# Driver.net
KiCad netlist of a schematic drawn in Altium Designer
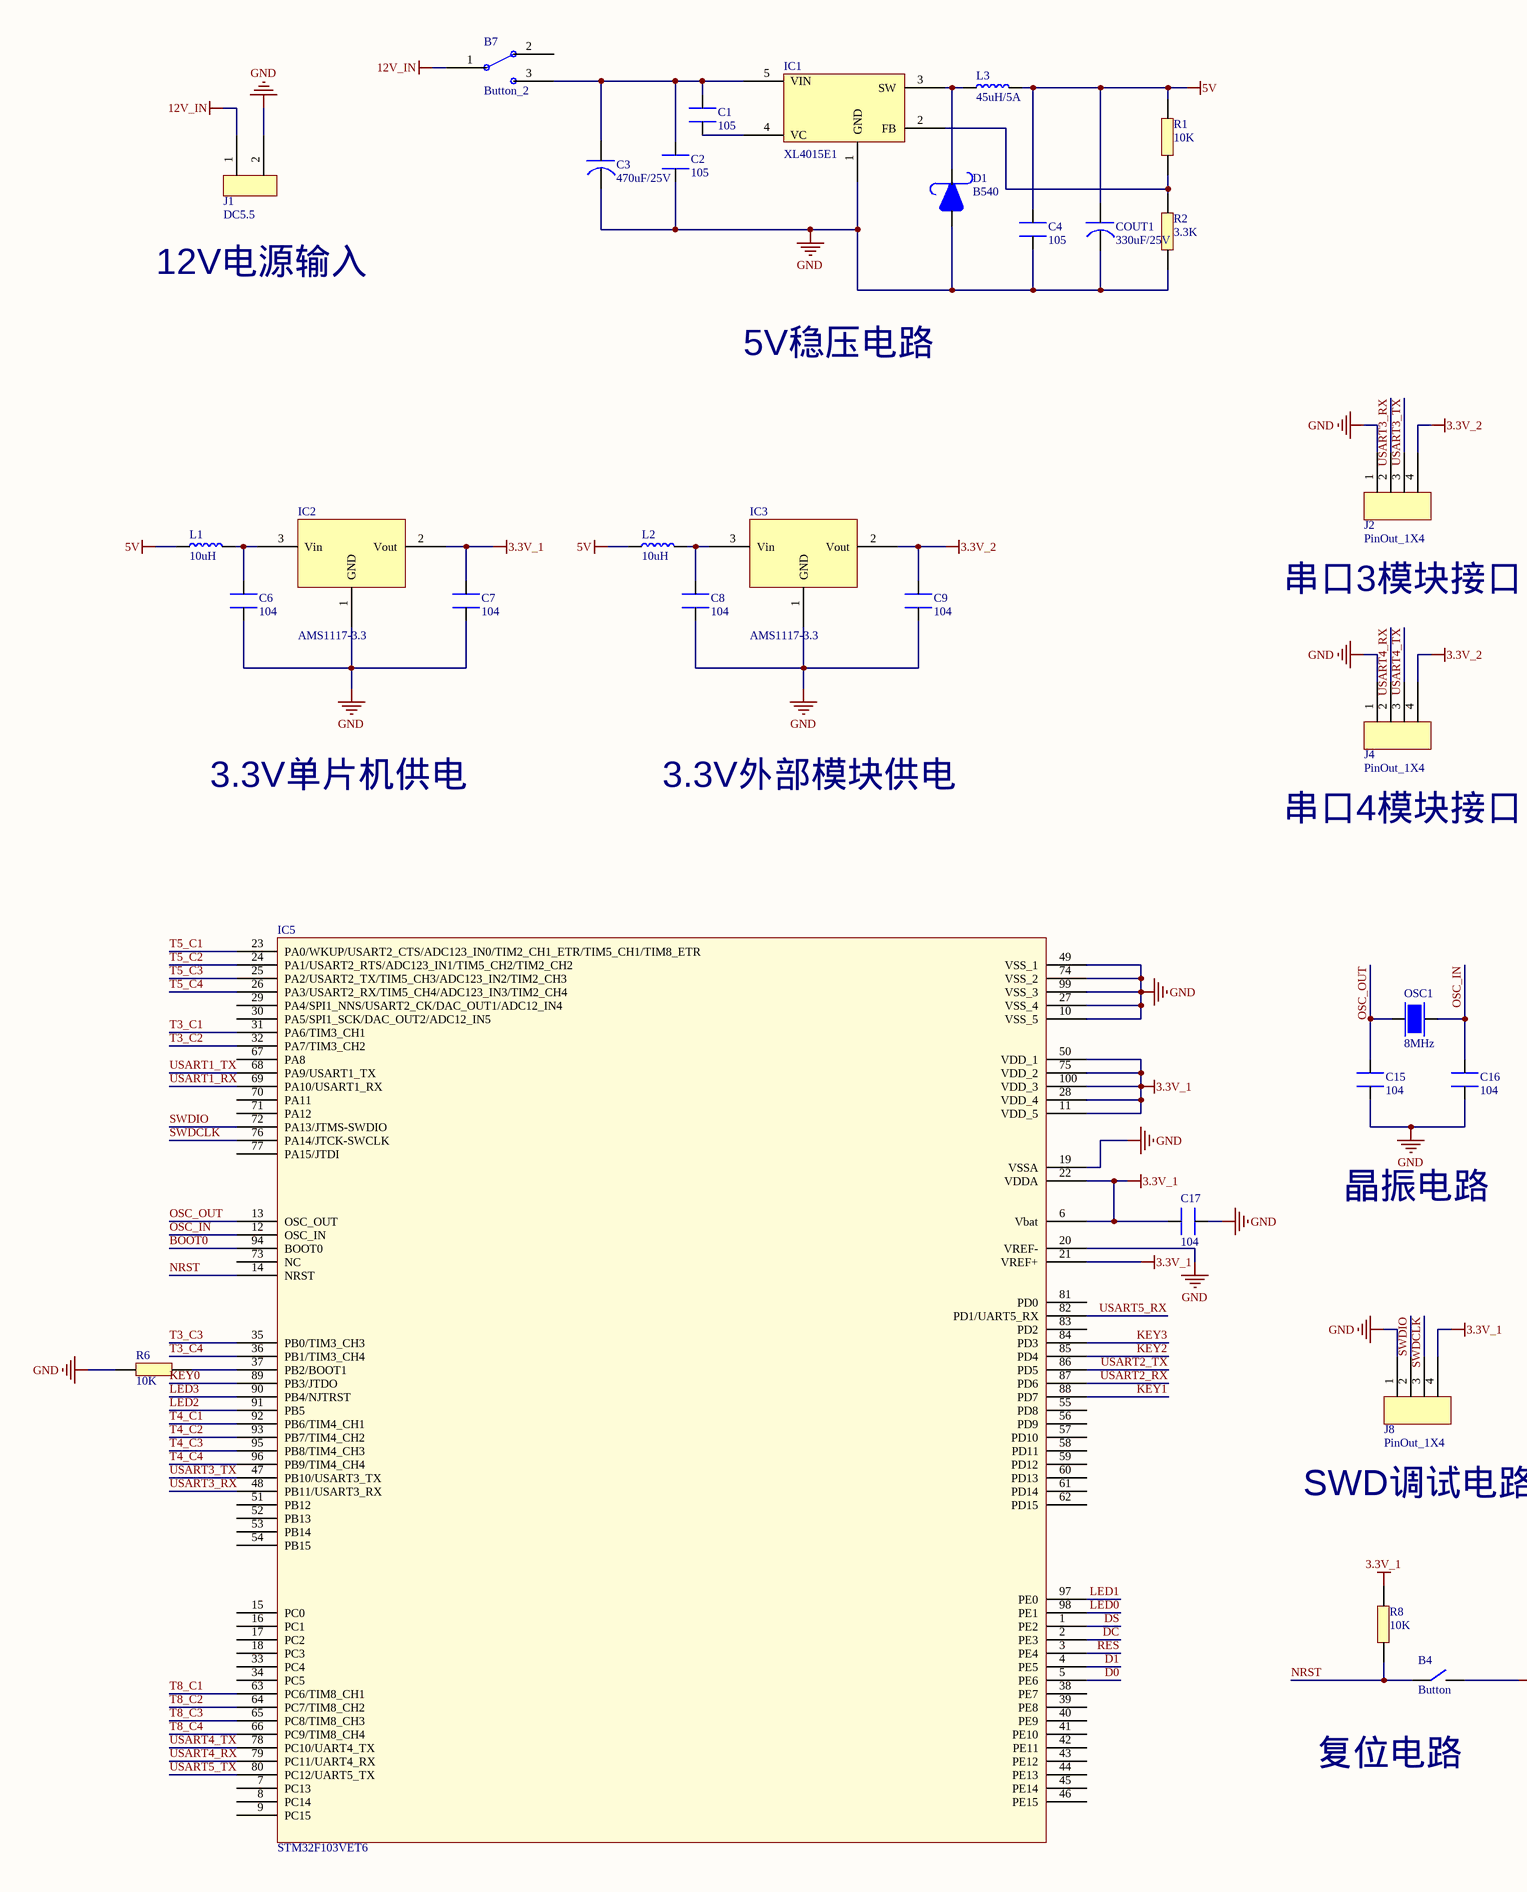
[diagram p0: Driver.SchDoc, left]
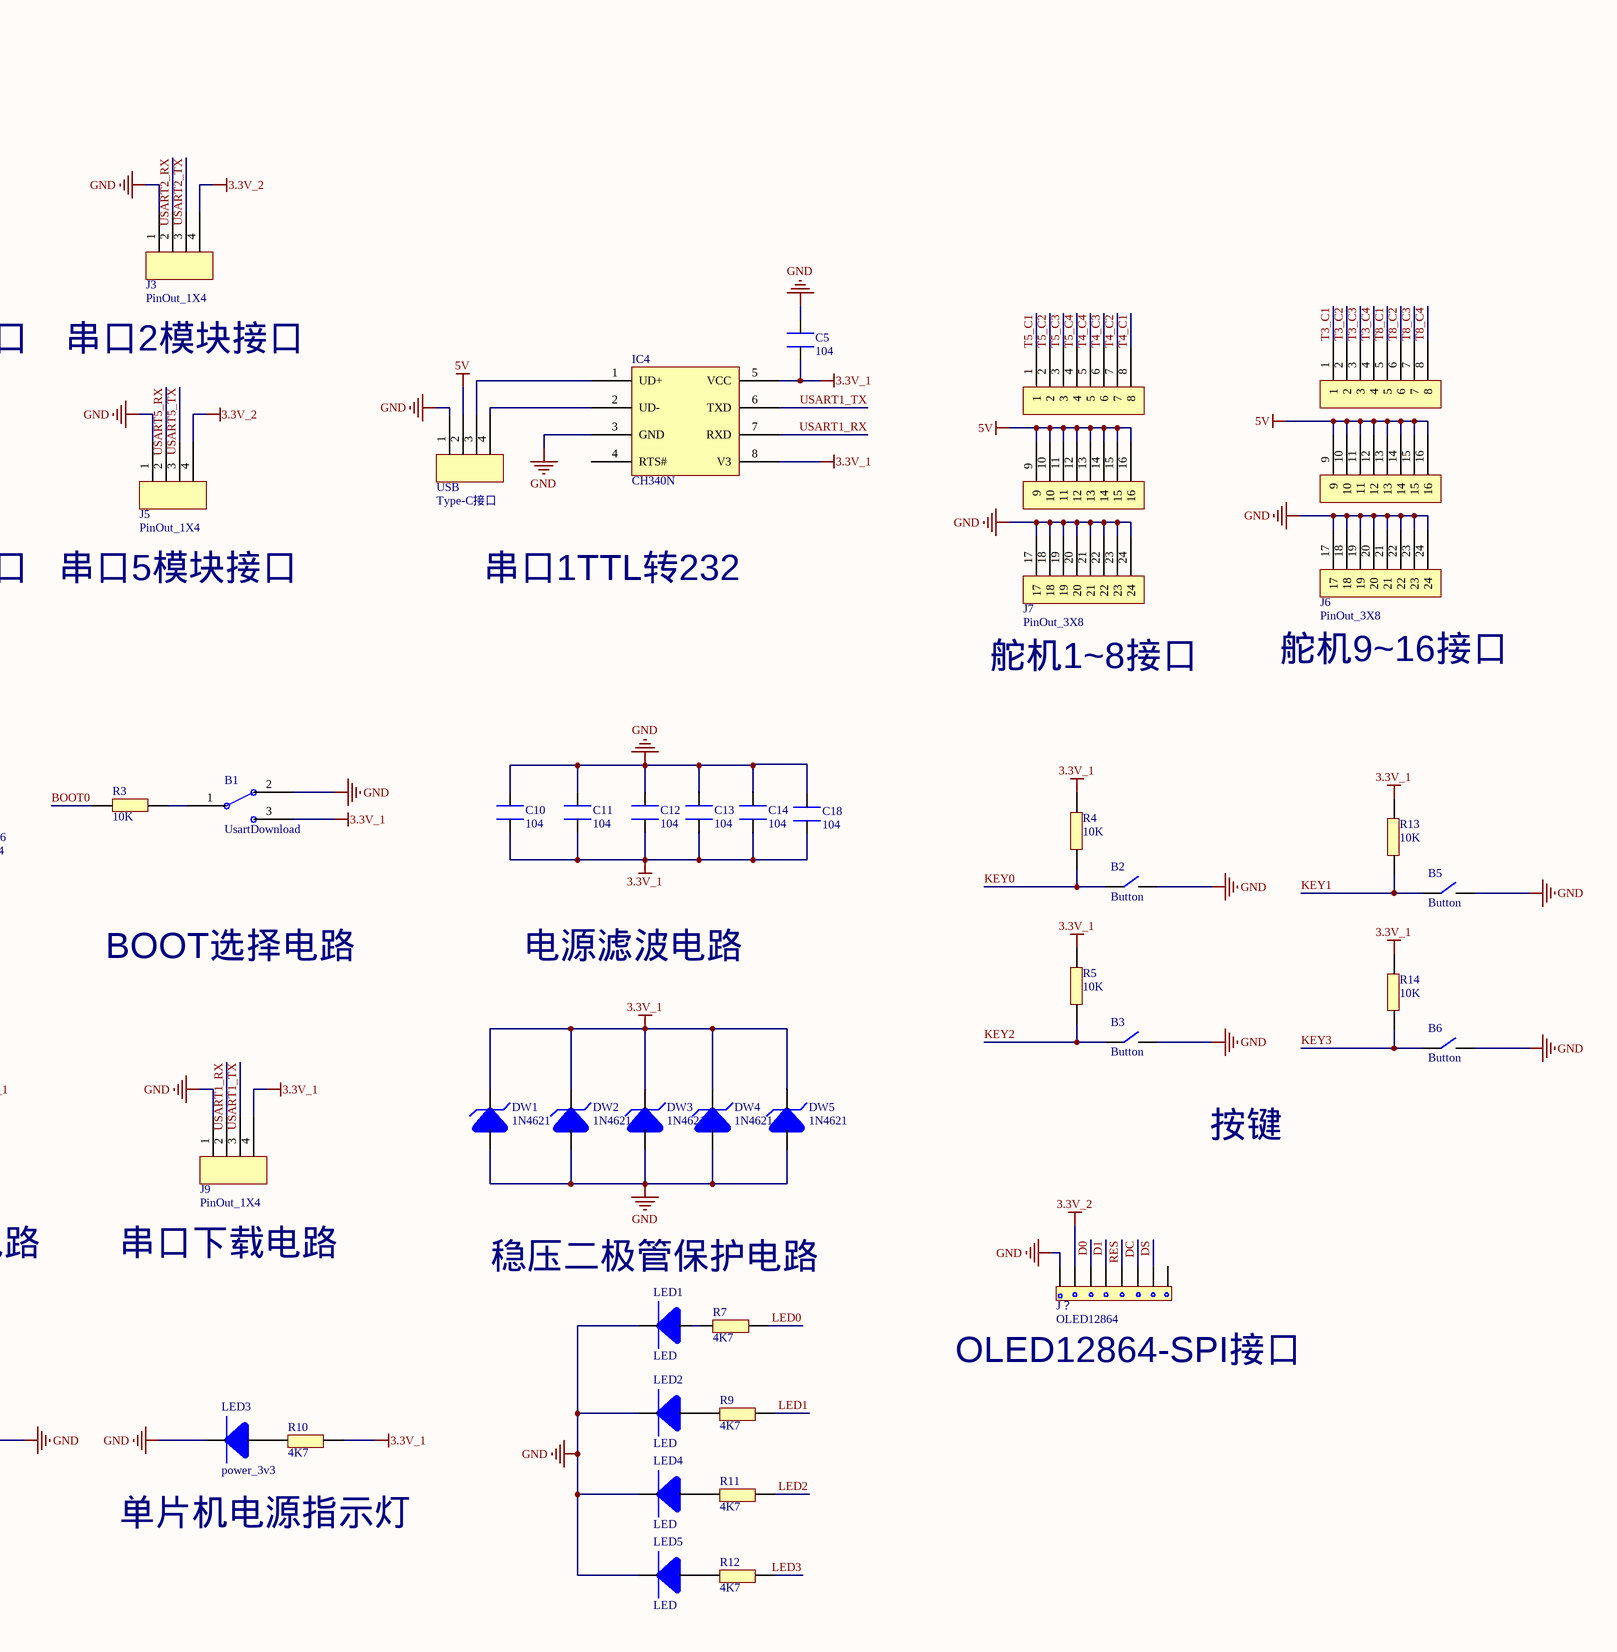
[diagram p1: Driver.SchDoc, right]

(export (version "E")
  (design (tool "Eeschema 10.0.6"))
  (components
    (comp (ref "B1")
      (value "UsartDownload")
      (footprint "BUTTON_7X7")
      (libsource (lib "altium-import") (part "root_0_Button_2_"))
    )
    (comp (ref "B2") (value "Button") (footprint "BUTTON") (libsource (lib "Driver") (part "Button")))
    (comp (ref "B3") (value "Button") (footprint "BUTTON") (libsource (lib "Driver") (part "Button")))
    (comp (ref "B4") (value "Button") (footprint "BUTTON") (libsource (lib "Driver") (part "Button")))
    (comp (ref "B5") (value "Button") (footprint "BUTTON") (libsource (lib "Driver") (part "Button")))
    (comp (ref "B6") (value "Button") (footprint "BUTTON") (libsource (lib "Driver") (part "Button")))
    (comp (ref "B7") (value "Button_2") (footprint "BUTTON_7X7") (libsource (lib "Driver") (part "Button_2")))
    (comp (ref "C1") (value "105") (footprint "0805") (libsource (lib "Driver") (part "CAP")))
    (comp (ref "C2") (value "105") (footprint "0805") (libsource (lib "Driver") (part "CAP")))
    (comp (ref "C3") (value "470uF/25V") (footprint "CM D(6.3X7.7)") (libsource (lib "Driver") (part "TAN")))
    (comp (ref "C4") (value "105") (footprint "0805") (libsource (lib "Driver") (part "CAP")))
    (comp (ref "C5") (value "104") (footprint "0805") (libsource (lib "Driver") (part "CAP")))
    (comp (ref "C6") (value "104") (footprint "0805") (libsource (lib "altium-import") (part "root_3_CAP_")))
    (comp (ref "C7") (value "104") (footprint "0805") (libsource (lib "altium-import") (part "root_3_CAP_")))
    (comp (ref "C8") (value "104") (footprint "0805") (libsource (lib "altium-import") (part "root_3_CAP_")))
    (comp (ref "C9") (value "104") (footprint "0805") (libsource (lib "altium-import") (part "root_3_CAP_")))
    (comp (ref "C10") (value "104") (footprint "0805") (libsource (lib "Driver") (part "CAP")))
    (comp (ref "C11") (value "104") (footprint "0805") (libsource (lib "Driver") (part "CAP")))
    (comp (ref "C12") (value "104") (footprint "0805") (libsource (lib "Driver") (part "CAP")))
    (comp (ref "C13") (value "104") (footprint "0805") (libsource (lib "Driver") (part "CAP")))
    (comp (ref "C14") (value "104") (footprint "0805") (libsource (lib "Driver") (part "CAP")))
    (comp (ref "C15") (value "104") (footprint "0805") (libsource (lib "Driver") (part "CAP")))
    (comp (ref "C16") (value "104") (footprint "0805") (libsource (lib "Driver") (part "CAP")))
    (comp (ref "C17") (value "104") (footprint "0805") (libsource (lib "Driver") (part "CAP")))
    (comp (ref "C18") (value "104") (footprint "0805") (libsource (lib "Driver") (part "CAP")))
    (comp (ref "COUT1")
      (value "330uF/25V")
      (footprint "CM D(6.3X7.7)")
      (libsource (lib "Driver") (part "TAN"))
    )
    (comp (ref "D1") (value "B540") (footprint "SMA/DO-214AC") (libsource (lib "Driver") (part "SBD")))
    (comp (ref "DW1") (value "1N4621") (footprint "1206") (libsource (lib "Driver") (part "DW")))
    (comp (ref "DW2") (value "1N4621") (footprint "1206") (libsource (lib "Driver") (part "DW")))
    (comp (ref "DW3") (value "1N4621") (footprint "1206") (libsource (lib "Driver") (part "DW")))
    (comp (ref "DW4") (value "1N4621") (footprint "1206") (libsource (lib "Driver") (part "DW")))
    (comp (ref "DW5") (value "1N4621") (footprint "1206") (libsource (lib "Driver") (part "DW")))
    (comp (ref "IC1") (value "XL4015E1") (footprint "TO236-5") (libsource (lib "Driver") (part "XL4015E1")))
    (comp (ref "IC2")
      (value "AMS1117-3.3")
      (footprint "AMS1117")
      (libsource (lib "Driver") (part "AMS1117-3.3"))
    )
    (comp (ref "IC3")
      (value "AMS1117-3.3")
      (footprint "AMS1117")
      (libsource (lib "Driver") (part "AMS1117-3.3"))
    )
    (comp (ref "IC4") (value "CH340N") (footprint "SOP-8") (libsource (lib "Driver") (part "CH340N")))
    (comp (ref "IC5")
      (value "STM32F103VET6")
      (footprint "LQFP100-14X14")
      (libsource (lib "altium-import") (part "root_0_STM32F103VET6_"))
    )
    (comp (ref "J1") (value "DC5.5") (footprint "DC_5.5") (libsource (lib "Driver") (part "PinOut_1X2")))
    (comp (ref "J2") (value "PinOut_1X4") (footprint "MX1.25") (libsource (lib "Driver") (part "PinOut_1X4")))
    (comp (ref "J3") (value "PinOut_1X4") (footprint "MX1.25") (libsource (lib "Driver") (part "PinOut_1X4")))
    (comp (ref "J4") (value "PinOut_1X4") (footprint "MX1.25") (libsource (lib "Driver") (part "PinOut_1X4")))
    (comp (ref "J5") (value "PinOut_1X4") (footprint "MX1.25") (libsource (lib "Driver") (part "PinOut_1X4")))
    (comp (ref "J6")
      (value "PinOut_3X8")
      (footprint "HEAD_3X8")
      (libsource (lib "Driver") (part "PinOut_3X8"))
    )
    (comp (ref "J7")
      (value "PinOut_3X8")
      (footprint "HEAD_3X8")
      (libsource (lib "Driver") (part "PinOut_3X8"))
    )
    (comp (ref "J8") (value "PinOut_1X4") (footprint "MX1.25") (libsource (lib "Driver") (part "PinOut_1X4")))
    (comp (ref "J9") (value "PinOut_1X4") (footprint "MX1.25") (libsource (lib "Driver") (part "PinOut_1X4")))
    (comp (ref "J？")
      (value "OLED12864")
      (footprint "HEAD_1X8")
      (libsource (lib "Driver") (part "PinOut_1X8"))
    )
    (comp (ref "L1") (value "10uH") (footprint "0630") (libsource (lib "Driver") (part "IND")))
    (comp (ref "L2") (value "10uH") (footprint "0630") (libsource (lib "Driver") (part "IND")))
    (comp (ref "L3") (value "45uH/5A") (footprint "0630") (libsource (lib "Driver") (part "IND")))
    (comp (ref "LED1") (value "LED") (footprint "1206") (libsource (lib "Driver") (part "LED")))
    (comp (ref "LED2") (value "LED") (footprint "1206") (libsource (lib "Driver") (part "LED")))
    (comp (ref "LED3") (value "power_3v3") (footprint "1206") (libsource (lib "Driver") (part "LED")))
    (comp (ref "LED4") (value "LED") (footprint "1206") (libsource (lib "Driver") (part "LED")))
    (comp (ref "LED5") (value "LED") (footprint "1206") (libsource (lib "Driver") (part "LED")))
    (comp (ref "OSC1") (value "8MHz") (footprint "OSC") (libsource (lib "Driver") (part "OSC")))
    (comp (ref "R1") (value "10K") (footprint "0805") (libsource (lib "") (part "RES_1")))
    (comp (ref "R2") (value "3.3K") (footprint "0805") (libsource (lib "") (part "RES_1")))
    (comp (ref "R3") (value "10K") (footprint "0805") (libsource (lib "Driver") (part "RES")))
    (comp (ref "R4") (value "10K") (footprint "0805") (libsource (lib "") (part "RES_1")))
    (comp (ref "R5") (value "10K") (footprint "0805") (libsource (lib "") (part "RES_1")))
    (comp (ref "R6") (value "10K") (footprint "0805") (libsource (lib "Driver") (part "RES")))
    (comp (ref "R7") (value "4K7") (footprint "0805") (libsource (lib "") (part "RES_2")))
    (comp (ref "R8") (value "10K") (footprint "0805") (libsource (lib "") (part "RES_1")))
    (comp (ref "R9") (value "4K7") (footprint "0805") (libsource (lib "") (part "RES_2")))
    (comp (ref "R10") (value "4K7") (footprint "0805") (libsource (lib "") (part "RES_2")))
    (comp (ref "R11") (value "4K7") (footprint "0805") (libsource (lib "") (part "RES_2")))
    (comp (ref "R12") (value "4K7") (footprint "0805") (libsource (lib "") (part "RES_2")))
    (comp (ref "R13") (value "10K") (footprint "0805") (libsource (lib "") (part "RES_1")))
    (comp (ref "R14") (value "10K") (footprint "0805") (libsource (lib "") (part "RES_1")))
    (comp (ref "USB") (value "Type-C接口") (footprint "Type-C") (libsource (lib "Driver") (part "PinOut_1X4")))
  )
  (nets
    (net (code "1") (name "/BOOT0") (class "Default")
      (node (ref "IC5") (pin "94") (pinfunction "BOOT0_94") (pintype "passive"))
      (node (ref "R3") (pin "1") (pinfunction "1_1") (pintype "passive"))
    )
    (net (code "2") (name "/D0") (class "Default")
      (node (ref "IC5") (pin "5") (pinfunction "PE6_5") (pintype "passive"))
      (node (ref "J？") (pin "3") (pinfunction "3_3") (pintype "passive"))
    )
    (net (code "3") (name "/D1") (class "Default")
      (node (ref "IC5") (pin "4") (pinfunction "PE5_4") (pintype "passive"))
      (node (ref "J？") (pin "4") (pinfunction "4_4") (pintype "passive"))
    )
    (net (code "4") (name "/DC") (class "Default")
      (node (ref "IC5") (pin "2") (pinfunction "PE3_2") (pintype "passive"))
      (node (ref "J？") (pin "6") (pinfunction "6_6") (pintype "passive"))
    )
    (net (code "5") (name "/DS") (class "Default")
      (node (ref "IC5") (pin "1") (pinfunction "PE2_1") (pintype "passive"))
      (node (ref "J？") (pin "7") (pinfunction "7_7") (pintype "passive"))
    )
    (net (code "6") (name "/KEY0") (class "Default")
      (node (ref "B2") (pin "1") (pinfunction "1_1") (pintype "passive"))
      (node (ref "IC5") (pin "89") (pinfunction "PB3/JTDO_89") (pintype "passive"))
      (node (ref "R4") (pin "1") (pinfunction "1_1") (pintype "passive"))
    )
    (net (code "7") (name "/KEY1") (class "Default")
      (node (ref "B5") (pin "1") (pinfunction "1_1") (pintype "passive"))
      (node (ref "IC5") (pin "88") (pinfunction "PD7_88") (pintype "passive"))
      (node (ref "R13") (pin "1") (pinfunction "1_1") (pintype "passive"))
    )
    (net (code "8") (name "/KEY2") (class "Default")
      (node (ref "B3") (pin "1") (pinfunction "1_1") (pintype "passive"))
      (node (ref "IC5") (pin "85") (pinfunction "PD4_85") (pintype "passive"))
      (node (ref "R5") (pin "1") (pinfunction "1_1") (pintype "passive"))
    )
    (net (code "9") (name "/KEY3") (class "Default")
      (node (ref "B6") (pin "1") (pinfunction "1_1") (pintype "passive"))
      (node (ref "IC5") (pin "84") (pinfunction "PD3_84") (pintype "passive"))
      (node (ref "R14") (pin "1") (pinfunction "1_1") (pintype "passive"))
    )
    (net (code "10") (name "/LED0") (class "Default")
      (node (ref "IC5") (pin "98") (pinfunction "PE1_98") (pintype "passive"))
      (node (ref "R7") (pin "1") (pinfunction "1_1") (pintype "passive"))
    )
    (net (code "11") (name "/LED1") (class "Default")
      (node (ref "IC5") (pin "97") (pinfunction "PE0_97") (pintype "passive"))
      (node (ref "R9") (pin "1") (pinfunction "1_1") (pintype "passive"))
    )
    (net (code "12") (name "/LED2") (class "Default")
      (node (ref "IC5") (pin "91") (pinfunction "PB5_91") (pintype "passive"))
      (node (ref "R11") (pin "1") (pinfunction "1_1") (pintype "passive"))
    )
    (net (code "13") (name "/LED3") (class "Default")
      (node (ref "IC5") (pin "90") (pinfunction "PB4/NJTRST_90") (pintype "passive"))
      (node (ref "R12") (pin "1") (pinfunction "1_1") (pintype "passive"))
    )
    (net (code "14") (name "/NRST") (class "Default")
      (node (ref "B4") (pin "1") (pinfunction "1_1") (pintype "passive"))
      (node (ref "IC5") (pin "14") (pinfunction "NRST_14") (pintype "passive"))
      (node (ref "R8") (pin "1") (pinfunction "1_1") (pintype "passive"))
    )
    (net (code "15") (name "/OSC_IN") (class "Default")
      (node (ref "C16") (pin "2") (pinfunction "2_2") (pintype "passive"))
      (node (ref "IC5") (pin "12") (pinfunction "OSC_IN_12") (pintype "passive"))
      (node (ref "OSC1") (pin "2") (pinfunction "2_2") (pintype "passive"))
    )
    (net (code "16") (name "/OSC_OUT") (class "Default")
      (node (ref "C15") (pin "2") (pinfunction "2_2") (pintype "passive"))
      (node (ref "IC5") (pin "13") (pinfunction "OSC_OUT_13") (pintype "passive"))
      (node (ref "OSC1") (pin "1") (pinfunction "1_1") (pintype "passive"))
    )
    (net (code "17") (name "/RES") (class "Default")
      (node (ref "IC5") (pin "3") (pinfunction "PE4_3") (pintype "passive"))
      (node (ref "J？") (pin "5") (pinfunction "5_5") (pintype "passive"))
    )
    (net (code "18") (name "/SWDCLK") (class "Default")
      (node (ref "IC5") (pin "76") (pinfunction "PA14/JTCK-SWCLK_76") (pintype "passive"))
      (node (ref "J8") (pin "3") (pinfunction "3_3") (pintype "passive"))
    )
    (net (code "19") (name "/SWDIO") (class "Default")
      (node (ref "IC5") (pin "72") (pinfunction "PA13/JTMS-SWDIO_72") (pintype "passive"))
      (node (ref "J8") (pin "2") (pinfunction "2_2") (pintype "passive"))
    )
    (net (code "20") (name "/T3_C1") (class "Default")
      (node (ref "IC5") (pin "31") (pinfunction "PA6/TIM3_CH1_31") (pintype "passive"))
      (node (ref "J6") (pin "1") (pinfunction "1_1") (pintype "passive"))
    )
    (net (code "21") (name "/T3_C2") (class "Default")
      (node (ref "IC5") (pin "32") (pinfunction "PA7/TIM3_CH2_32") (pintype "passive"))
      (node (ref "J6") (pin "2") (pinfunction "2_2") (pintype "passive"))
    )
    (net (code "22") (name "/T3_C3") (class "Default")
      (node (ref "IC5") (pin "35") (pinfunction "PB0/TIM3_CH3_35") (pintype "passive"))
      (node (ref "J6") (pin "3") (pinfunction "3_3") (pintype "passive"))
    )
    (net (code "23") (name "/T3_C4") (class "Default")
      (node (ref "IC5") (pin "36") (pinfunction "PB1/TIM3_CH4_36") (pintype "passive"))
      (node (ref "J6") (pin "4") (pinfunction "4_4") (pintype "passive"))
    )
    (net (code "24") (name "/T4_C1") (class "Default")
      (node (ref "IC5") (pin "92") (pinfunction "PB6/TIM4_CH1_92") (pintype "passive"))
      (node (ref "J7") (pin "8") (pinfunction "8_8") (pintype "passive"))
    )
    (net (code "25") (name "/T4_C2") (class "Default")
      (node (ref "IC5") (pin "93") (pinfunction "PB7/TIM4_CH2_93") (pintype "passive"))
      (node (ref "J7") (pin "7") (pinfunction "7_7") (pintype "passive"))
    )
    (net (code "26") (name "/T4_C3") (class "Default")
      (node (ref "IC5") (pin "95") (pinfunction "PB8/TIM4_CH3_95") (pintype "passive"))
      (node (ref "J7") (pin "6") (pinfunction "6_6") (pintype "passive"))
    )
    (net (code "27") (name "/T4_C4") (class "Default")
      (node (ref "IC5") (pin "96") (pinfunction "PB9/TIM4_CH4_96") (pintype "passive"))
      (node (ref "J7") (pin "5") (pinfunction "5_5") (pintype "passive"))
    )
    (net (code "28") (name "/T5_C1") (class "Default")
      (node (ref "IC5") (pin "23") (pinfunction "PA0/WKUP/USART2_CTS/ADC123_IN0/TIM2_CH1_ETR/TIM5_CH1/TIM8_ETR_23") (pintype "passive"))
      (node (ref "J7") (pin "1") (pinfunction "1_1") (pintype "passive"))
    )
    (net (code "29") (name "/T5_C2") (class "Default")
      (node (ref "IC5") (pin "24") (pinfunction "PA1/USART2_RTS/ADC123_IN1/TIM5_CH2/TIM2_CH2_24") (pintype "passive"))
      (node (ref "J7") (pin "2") (pinfunction "2_2") (pintype "passive"))
    )
    (net (code "30") (name "/T5_C3") (class "Default")
      (node (ref "IC5") (pin "25") (pinfunction "PA2/USART2_TX/TIM5_CH3/ADC123_IN2/TIM2_CH3_25") (pintype "passive"))
      (node (ref "J7") (pin "3") (pinfunction "3_3") (pintype "passive"))
    )
    (net (code "31") (name "/T5_C4") (class "Default")
      (node (ref "IC5") (pin "26") (pinfunction "PA3/USART2_RX/TIM5_CH4/ADC123_IN3/TIM2_CH4_26") (pintype "passive"))
      (node (ref "J7") (pin "4") (pinfunction "4_4") (pintype "passive"))
    )
    (net (code "32") (name "/T8_C1") (class "Default")
      (node (ref "IC5") (pin "63") (pinfunction "PC6/TIM8_CH1_63") (pintype "passive"))
      (node (ref "J6") (pin "5") (pinfunction "5_5") (pintype "passive"))
    )
    (net (code "33") (name "/T8_C2") (class "Default")
      (node (ref "IC5") (pin "64") (pinfunction "PC7/TIM8_CH2_64") (pintype "passive"))
      (node (ref "J6") (pin "6") (pinfunction "6_6") (pintype "passive"))
    )
    (net (code "34") (name "/T8_C3") (class "Default")
      (node (ref "IC5") (pin "65") (pinfunction "PC8/TIM8_CH3_65") (pintype "passive"))
      (node (ref "J6") (pin "7") (pinfunction "7_7") (pintype "passive"))
    )
    (net (code "35") (name "/T8_C4") (class "Default")
      (node (ref "IC5") (pin "66") (pinfunction "PC9/TIM8_CH4_66") (pintype "passive"))
      (node (ref "J6") (pin "8") (pinfunction "8_8") (pintype "passive"))
    )
    (net (code "36") (name "/USART1_RX") (class "Default")
      (node (ref "IC4") (pin "7") (pinfunction "RXD_7") (pintype "passive"))
      (node (ref "IC5") (pin "69") (pinfunction "PA10/USART1_RX_69") (pintype "passive"))
      (node (ref "J9") (pin "2") (pinfunction "2_2") (pintype "passive"))
    )
    (net (code "37") (name "/USART1_TX") (class "Default")
      (node (ref "IC4") (pin "6") (pinfunction "TXD_6") (pintype "passive"))
      (node (ref "IC5") (pin "68") (pinfunction "PA9/USART1_TX_68") (pintype "passive"))
      (node (ref "J9") (pin "3") (pinfunction "3_3") (pintype "passive"))
    )
    (net (code "38") (name "/USART2_RX") (class "Default")
      (node (ref "IC5") (pin "87") (pinfunction "PD6_87") (pintype "passive"))
      (node (ref "J3") (pin "2") (pinfunction "2_2") (pintype "passive"))
    )
    (net (code "39") (name "/USART2_TX") (class "Default")
      (node (ref "IC5") (pin "86") (pinfunction "PD5_86") (pintype "passive"))
      (node (ref "J3") (pin "3") (pinfunction "3_3") (pintype "passive"))
    )
    (net (code "40") (name "/USART3_RX") (class "Default")
      (node (ref "IC5") (pin "48") (pinfunction "PB11/USART3_RX_48") (pintype "passive"))
      (node (ref "J2") (pin "2") (pinfunction "2_2") (pintype "passive"))
    )
    (net (code "41") (name "/USART3_TX") (class "Default")
      (node (ref "IC5") (pin "47") (pinfunction "PB10/USART3_TX_47") (pintype "passive"))
      (node (ref "J2") (pin "3") (pinfunction "3_3") (pintype "passive"))
    )
    (net (code "42") (name "/USART4_RX") (class "Default")
      (node (ref "IC5") (pin "79") (pinfunction "PC11/UART4_RX_79") (pintype "passive"))
      (node (ref "J4") (pin "2") (pinfunction "2_2") (pintype "passive"))
    )
    (net (code "43") (name "/USART4_TX") (class "Default")
      (node (ref "IC5") (pin "78") (pinfunction "PC10/UART4_TX_78") (pintype "passive"))
      (node (ref "J4") (pin "3") (pinfunction "3_3") (pintype "passive"))
    )
    (net (code "44") (name "/USART5_RX") (class "Default")
      (node (ref "IC5") (pin "82") (pinfunction "PD1/UART5_RX_82") (pintype "passive"))
      (node (ref "J5") (pin "2") (pinfunction "2_2") (pintype "passive"))
    )
    (net (code "45") (name "/USART5_TX") (class "Default")
      (node (ref "IC5") (pin "80") (pinfunction "PC12/UART5_TX_80") (pintype "passive"))
      (node (ref "J5") (pin "3") (pinfunction "3_3") (pintype "passive"))
    )
    (net (code "46") (name "3.3V_1") (class "Default")
      (node (ref "B1") (pin "3") (pinfunction "3_3") (pintype "passive"))
      (node (ref "C10") (pin "1") (pinfunction "1_1") (pintype "passive"))
      (node (ref "C11") (pin "1") (pinfunction "1_1") (pintype "passive"))
      (node (ref "C12") (pin "1") (pinfunction "1_1") (pintype "passive"))
      (node (ref "C13") (pin "1") (pinfunction "1_1") (pintype "passive"))
      (node (ref "C14") (pin "1") (pinfunction "1_1") (pintype "passive"))
      (node (ref "C17") (pin "1") (pinfunction "1_1") (pintype "passive"))
      (node (ref "C18") (pin "1") (pinfunction "1_1") (pintype "passive"))
      (node (ref "C5") (pin "1") (pinfunction "1_1") (pintype "passive"))
      (node (ref "C7") (pin "1") (pinfunction "1_1") (pintype "passive"))
      (node (ref "DW1") (pin "1") (pinfunction "-_1") (pintype "passive"))
      (node (ref "DW2") (pin "1") (pinfunction "-_1") (pintype "passive"))
      (node (ref "DW3") (pin "1") (pinfunction "-_1") (pintype "passive"))
      (node (ref "DW4") (pin "1") (pinfunction "-_1") (pintype "passive"))
      (node (ref "DW5") (pin "1") (pinfunction "-_1") (pintype "passive"))
      (node (ref "IC2") (pin "2") (pinfunction "Vout_2") (pintype "passive"))
      (node (ref "IC4") (pin "5") (pinfunction "VCC_5") (pintype "passive"))
      (node (ref "IC4") (pin "8") (pinfunction "V3_8") (pintype "passive"))
      (node (ref "IC5") (pin "100") (pinfunction "VDD_3_100") (pintype "passive"))
      (node (ref "IC5") (pin "11") (pinfunction "VDD_5_11") (pintype "passive"))
      (node (ref "IC5") (pin "21") (pinfunction "VREF+_21") (pintype "passive"))
      (node (ref "IC5") (pin "22") (pinfunction "VDDA_22") (pintype "passive"))
      (node (ref "IC5") (pin "28") (pinfunction "VDD_4_28") (pintype "passive"))
      (node (ref "IC5") (pin "50") (pinfunction "VDD_1_50") (pintype "passive"))
      (node (ref "IC5") (pin "6") (pinfunction "Vbat_6") (pintype "passive"))
      (node (ref "IC5") (pin "75") (pinfunction "VDD_2_75") (pintype "passive"))
      (node (ref "J8") (pin "4") (pinfunction "4_4") (pintype "passive"))
      (node (ref "J9") (pin "4") (pinfunction "4_4") (pintype "passive"))
      (node (ref "R10") (pin "1") (pinfunction "1_1") (pintype "passive"))
      (node (ref "R13") (pin "2") (pinfunction "2_2") (pintype "passive"))
      (node (ref "R14") (pin "2") (pinfunction "2_2") (pintype "passive"))
      (node (ref "R4") (pin "2") (pinfunction "2_2") (pintype "passive"))
      (node (ref "R5") (pin "2") (pinfunction "2_2") (pintype "passive"))
      (node (ref "R8") (pin "2") (pinfunction "2_2") (pintype "passive"))
    )
    (net (code "47") (name "3.3V_2") (class "Default")
      (node (ref "C9") (pin "1") (pinfunction "1_1") (pintype "passive"))
      (node (ref "IC3") (pin "2") (pinfunction "Vout_2") (pintype "passive"))
      (node (ref "J2") (pin "4") (pinfunction "4_4") (pintype "passive"))
      (node (ref "J3") (pin "4") (pinfunction "4_4") (pintype "passive"))
      (node (ref "J4") (pin "4") (pinfunction "4_4") (pintype "passive"))
      (node (ref "J5") (pin "4") (pinfunction "4_4") (pintype "passive"))
      (node (ref "J？") (pin "2") (pinfunction "2_2") (pintype "passive"))
    )
    (net (code "48") (name "5V") (class "Default")
      (node (ref "C4") (pin "2") (pinfunction "2_2") (pintype "passive"))
      (node (ref "COUT1") (pin "2") (pinfunction "2_2") (pintype "passive"))
      (node (ref "J6") (pin "10") (pinfunction "10_10") (pintype "passive"))
      (node (ref "J6") (pin "11") (pinfunction "11_11") (pintype "passive"))
      (node (ref "J6") (pin "12") (pinfunction "12_12") (pintype "passive"))
      (node (ref "J6") (pin "13") (pinfunction "13_13") (pintype "passive"))
      (node (ref "J6") (pin "14") (pinfunction "14_14") (pintype "passive"))
      (node (ref "J6") (pin "15") (pinfunction "15_15") (pintype "passive"))
      (node (ref "J6") (pin "16") (pinfunction "16_16") (pintype "passive"))
      (node (ref "J6") (pin "9") (pinfunction "9_9") (pintype "passive"))
      (node (ref "J7") (pin "10") (pinfunction "10_10") (pintype "passive"))
      (node (ref "J7") (pin "11") (pinfunction "11_11") (pintype "passive"))
      (node (ref "J7") (pin "12") (pinfunction "12_12") (pintype "passive"))
      (node (ref "J7") (pin "13") (pinfunction "13_13") (pintype "passive"))
      (node (ref "J7") (pin "14") (pinfunction "14_14") (pintype "passive"))
      (node (ref "J7") (pin "15") (pinfunction "15_15") (pintype "passive"))
      (node (ref "J7") (pin "16") (pinfunction "16_16") (pintype "passive"))
      (node (ref "J7") (pin "9") (pinfunction "9_9") (pintype "passive"))
      (node (ref "L1") (pin "1") (pinfunction "1_1") (pintype "passive"))
      (node (ref "L2") (pin "1") (pinfunction "1_1") (pintype "passive"))
      (node (ref "L3") (pin "2") (pinfunction "2_2") (pintype "passive"))
      (node (ref "R1") (pin "2") (pinfunction "2_2") (pintype "passive"))
      (node (ref "USB") (pin "2") (pinfunction "2_2") (pintype "passive"))
    )
    (net (code "49") (name "12V_IN") (class "Default")
      (node (ref "B7") (pin "1") (pinfunction "1_1") (pintype "passive"))
      (node (ref "J1") (pin "1") (pinfunction "1_1") (pintype "passive"))
    )
    (net (code "50") (name "GND") (class "Default")
      (node (ref "B1") (pin "2") (pinfunction "2_2") (pintype "passive"))
      (node (ref "B2") (pin "2") (pinfunction "2_2") (pintype "passive"))
      (node (ref "B3") (pin "2") (pinfunction "2_2") (pintype "passive"))
      (node (ref "B4") (pin "2") (pinfunction "2_2") (pintype "passive"))
      (node (ref "B5") (pin "2") (pinfunction "2_2") (pintype "passive"))
      (node (ref "B6") (pin "2") (pinfunction "2_2") (pintype "passive"))
      (node (ref "C10") (pin "2") (pinfunction "2_2") (pintype "passive"))
      (node (ref "C11") (pin "2") (pinfunction "2_2") (pintype "passive"))
      (node (ref "C12") (pin "2") (pinfunction "2_2") (pintype "passive"))
      (node (ref "C13") (pin "2") (pinfunction "2_2") (pintype "passive"))
      (node (ref "C14") (pin "2") (pinfunction "2_2") (pintype "passive"))
      (node (ref "C15") (pin "1") (pinfunction "1_1") (pintype "passive"))
      (node (ref "C16") (pin "1") (pinfunction "1_1") (pintype "passive"))
      (node (ref "C17") (pin "2") (pinfunction "2_2") (pintype "passive"))
      (node (ref "C18") (pin "2") (pinfunction "2_2") (pintype "passive"))
      (node (ref "C2") (pin "1") (pinfunction "1_1") (pintype "passive"))
      (node (ref "C3") (pin "1") (pinfunction "1_1") (pintype "passive"))
      (node (ref "C4") (pin "1") (pinfunction "1_1") (pintype "passive"))
      (node (ref "C5") (pin "2") (pinfunction "2_2") (pintype "passive"))
      (node (ref "C6") (pin "2") (pinfunction "2_2") (pintype "passive"))
      (node (ref "C7") (pin "2") (pinfunction "2_2") (pintype "passive"))
      (node (ref "C8") (pin "2") (pinfunction "2_2") (pintype "passive"))
      (node (ref "C9") (pin "2") (pinfunction "2_2") (pintype "passive"))
      (node (ref "COUT1") (pin "1") (pinfunction "1_1") (pintype "passive"))
      (node (ref "D1") (pin "2") (pinfunction "2_2") (pintype "passive"))
      (node (ref "DW1") (pin "2") (pinfunction "+_2") (pintype "passive"))
      (node (ref "DW2") (pin "2") (pinfunction "+_2") (pintype "passive"))
      (node (ref "DW3") (pin "2") (pinfunction "+_2") (pintype "passive"))
      (node (ref "DW4") (pin "2") (pinfunction "+_2") (pintype "passive"))
      (node (ref "DW5") (pin "2") (pinfunction "+_2") (pintype "passive"))
      (node (ref "IC1") (pin "1") (pinfunction "GND_1") (pintype "passive"))
      (node (ref "IC2") (pin "1") (pinfunction "GND_1") (pintype "passive"))
      (node (ref "IC3") (pin "1") (pinfunction "GND_1") (pintype "passive"))
      (node (ref "IC4") (pin "3") (pinfunction "GND_3") (pintype "passive"))
      (node (ref "IC5") (pin "10") (pinfunction "VSS_5_10") (pintype "passive"))
      (node (ref "IC5") (pin "19") (pinfunction "VSSA_19") (pintype "passive"))
      (node (ref "IC5") (pin "20") (pinfunction "VREF-_20") (pintype "passive"))
      (node (ref "IC5") (pin "27") (pinfunction "VSS_4_27") (pintype "passive"))
      (node (ref "IC5") (pin "49") (pinfunction "VSS_1_49") (pintype "passive"))
      (node (ref "IC5") (pin "74") (pinfunction "VSS_2_74") (pintype "passive"))
      (node (ref "IC5") (pin "99") (pinfunction "VSS_3_99") (pintype "passive"))
      (node (ref "J1") (pin "2") (pinfunction "2_2") (pintype "passive"))
      (node (ref "J2") (pin "1") (pinfunction "1_1") (pintype "passive"))
      (node (ref "J3") (pin "1") (pinfunction "1_1") (pintype "passive"))
      (node (ref "J4") (pin "1") (pinfunction "1_1") (pintype "passive"))
      (node (ref "J5") (pin "1") (pinfunction "1_1") (pintype "passive"))
      (node (ref "J6") (pin "17") (pinfunction "17_17") (pintype "passive"))
      (node (ref "J6") (pin "18") (pinfunction "18_18") (pintype "passive"))
      (node (ref "J6") (pin "19") (pinfunction "19_19") (pintype "passive"))
      (node (ref "J6") (pin "20") (pinfunction "20_20") (pintype "passive"))
      (node (ref "J6") (pin "21") (pinfunction "21_21") (pintype "passive"))
      (node (ref "J6") (pin "22") (pinfunction "22_22") (pintype "passive"))
      (node (ref "J6") (pin "23") (pinfunction "23_23") (pintype "passive"))
      (node (ref "J6") (pin "24") (pinfunction "24_24") (pintype "passive"))
      (node (ref "J7") (pin "17") (pinfunction "17_17") (pintype "passive"))
      (node (ref "J7") (pin "18") (pinfunction "18_18") (pintype "passive"))
      (node (ref "J7") (pin "19") (pinfunction "19_19") (pintype "passive"))
      (node (ref "J7") (pin "20") (pinfunction "20_20") (pintype "passive"))
      (node (ref "J7") (pin "21") (pinfunction "21_21") (pintype "passive"))
      (node (ref "J7") (pin "22") (pinfunction "22_22") (pintype "passive"))
      (node (ref "J7") (pin "23") (pinfunction "23_23") (pintype "passive"))
      (node (ref "J7") (pin "24") (pinfunction "24_24") (pintype "passive"))
      (node (ref "J8") (pin "1") (pinfunction "1_1") (pintype "passive"))
      (node (ref "J9") (pin "1") (pinfunction "1_1") (pintype "passive"))
      (node (ref "J？") (pin "1") (pinfunction "1_1") (pintype "passive"))
      (node (ref "LED1") (pin "1") (pinfunction "-_1") (pintype "passive"))
      (node (ref "LED2") (pin "1") (pinfunction "-_1") (pintype "passive"))
      (node (ref "LED3") (pin "1") (pinfunction "-_1") (pintype "passive"))
      (node (ref "LED4") (pin "1") (pinfunction "-_1") (pintype "passive"))
      (node (ref "LED5") (pin "1") (pinfunction "-_1") (pintype "passive"))
      (node (ref "R2") (pin "1") (pinfunction "1_1") (pintype "passive"))
      (node (ref "R6") (pin "1") (pinfunction "1_1") (pintype "passive"))
      (node (ref "USB") (pin "1") (pinfunction "1_1") (pintype "passive"))
    )
    (net (code "51") (name "Net-(B1-Pad1)") (class "Default")
      (node (ref "B1") (pin "1") (pinfunction "1_1") (pintype "passive"))
      (node (ref "R3") (pin "2") (pinfunction "2_2") (pintype "passive"))
    )
    (net (code "52") (name "Net-(IC1-FB)") (class "Default")
      (node (ref "IC1") (pin "2") (pinfunction "FB_2") (pintype "passive"))
      (node (ref "R1") (pin "1") (pinfunction "1_1") (pintype "passive"))
      (node (ref "R2") (pin "2") (pinfunction "2_2") (pintype "passive"))
    )
    (net (code "53") (name "Net-(IC1-SW)") (class "Default")
      (node (ref "D1") (pin "1") (pinfunction "1_1") (pintype "passive"))
      (node (ref "IC1") (pin "3") (pinfunction "SW_3") (pintype "passive"))
      (node (ref "L3") (pin "1") (pinfunction "1_1") (pintype "passive"))
    )
    (net (code "54") (name "Net-(IC1-VC)") (class "Default")
      (node (ref "C1") (pin "1") (pinfunction "1_1") (pintype "passive"))
      (node (ref "IC1") (pin "4") (pinfunction "VC_4") (pintype "passive"))
    )
    (net (code "55") (name "Net-(IC1-VIN)") (class "Default")
      (node (ref "B7") (pin "3") (pinfunction "3_3") (pintype "passive"))
      (node (ref "C1") (pin "2") (pinfunction "2_2") (pintype "passive"))
      (node (ref "C2") (pin "2") (pinfunction "2_2") (pintype "passive"))
      (node (ref "C3") (pin "2") (pinfunction "2_2") (pintype "passive"))
      (node (ref "IC1") (pin "5") (pinfunction "VIN_5") (pintype "passive"))
    )
    (net (code "56") (name "Net-(IC2-Vin)") (class "Default")
      (node (ref "C6") (pin "1") (pinfunction "1_1") (pintype "passive"))
      (node (ref "IC2") (pin "3") (pinfunction "Vin_3") (pintype "passive"))
      (node (ref "L1") (pin "2") (pinfunction "2_2") (pintype "passive"))
    )
    (net (code "57") (name "Net-(IC3-Vin)") (class "Default")
      (node (ref "C8") (pin "1") (pinfunction "1_1") (pintype "passive"))
      (node (ref "IC3") (pin "3") (pinfunction "Vin_3") (pintype "passive"))
      (node (ref "L2") (pin "2") (pinfunction "2_2") (pintype "passive"))
    )
    (net (code "58") (name "Net-(IC4-UD+)") (class "Default")
      (node (ref "IC4") (pin "1") (pinfunction "UD+_1") (pintype "passive"))
      (node (ref "USB") (pin "3") (pinfunction "3_3") (pintype "passive"))
    )
    (net (code "59") (name "Net-(IC4-UD-)") (class "Default")
      (node (ref "IC4") (pin "2") (pinfunction "UD-_2") (pintype "passive"))
      (node (ref "USB") (pin "4") (pinfunction "4_4") (pintype "passive"))
    )
    (net (code "60") (name "Net-(IC5-PB2{slash}BOOT1)") (class "Default")
      (node (ref "IC5") (pin "37") (pinfunction "PB2/BOOT1_37") (pintype "passive"))
      (node (ref "R6") (pin "2") (pinfunction "2_2") (pintype "passive"))
    )
    (net (code "61") (name "Net-(LED1-+)") (class "Default")
      (node (ref "LED1") (pin "2") (pinfunction "+_2") (pintype "passive"))
      (node (ref "R7") (pin "2") (pinfunction "2_2") (pintype "passive"))
    )
    (net (code "62") (name "Net-(LED2-+)") (class "Default")
      (node (ref "LED2") (pin "2") (pinfunction "+_2") (pintype "passive"))
      (node (ref "R9") (pin "2") (pinfunction "2_2") (pintype "passive"))
    )
    (net (code "63") (name "Net-(LED3-+)") (class "Default")
      (node (ref "LED3") (pin "2") (pinfunction "+_2") (pintype "passive"))
      (node (ref "R10") (pin "2") (pinfunction "2_2") (pintype "passive"))
    )
    (net (code "64") (name "Net-(LED4-+)") (class "Default")
      (node (ref "LED4") (pin "2") (pinfunction "+_2") (pintype "passive"))
      (node (ref "R11") (pin "2") (pinfunction "2_2") (pintype "passive"))
    )
    (net (code "65") (name "Net-(LED5-+)") (class "Default")
      (node (ref "LED5") (pin "2") (pinfunction "+_2") (pintype "passive"))
      (node (ref "R12") (pin "2") (pinfunction "2_2") (pintype "passive"))
    )
    (net (code "66") (name "unconnected-(B7-Pad2)") (class "Default")
      (node (ref "B7") (pin "2") (pinfunction "2_2") (pintype "passive"))
    )
    (net (code "67") (name "unconnected-(IC4-RTS#-Pad4)") (class "Default")
      (node (ref "IC4") (pin "4") (pinfunction "RTS#_4") (pintype "passive"))
    )
    (net (code "68") (name "unconnected-(IC5-NC-Pad73)") (class "Default")
      (node (ref "IC5") (pin "73") (pinfunction "NC_73") (pintype "passive"))
    )
    (net (code "69") (name "unconnected-(IC5-PA4{slash}SPI1_NNS{slash}USART2_CK{slash}DAC_OUT1{slash}ADC12_IN4-Pad29)") (class "Default")
      (node (ref "IC5") (pin "29") (pinfunction "PA4/SPI1_NNS/USART2_CK/DAC_OUT1/ADC12_IN4_29") (pintype "passive"))
    )
    (net (code "70") (name "unconnected-(IC5-PA5{slash}SPI1_SCK{slash}DAC_OUT2{slash}ADC12_IN5-Pad30)") (class "Default")
      (node (ref "IC5") (pin "30") (pinfunction "PA5/SPI1_SCK/DAC_OUT2/ADC12_IN5_30") (pintype "passive"))
    )
    (net (code "71") (name "unconnected-(IC5-PA8-Pad67)") (class "Default")
      (node (ref "IC5") (pin "67") (pinfunction "PA8_67") (pintype "passive"))
    )
    (net (code "72") (name "unconnected-(IC5-PA11-Pad70)") (class "Default")
      (node (ref "IC5") (pin "70") (pinfunction "PA11_70") (pintype "passive"))
    )
    (net (code "73") (name "unconnected-(IC5-PA12-Pad71)") (class "Default")
      (node (ref "IC5") (pin "71") (pinfunction "PA12_71") (pintype "passive"))
    )
    (net (code "74") (name "unconnected-(IC5-PA15{slash}JTDI-Pad77)") (class "Default")
      (node (ref "IC5") (pin "77") (pinfunction "PA15/JTDI_77") (pintype "passive"))
    )
    (net (code "75") (name "unconnected-(IC5-PB12-Pad51)") (class "Default")
      (node (ref "IC5") (pin "51") (pinfunction "PB12_51") (pintype "passive"))
    )
    (net (code "76") (name "unconnected-(IC5-PB13-Pad52)") (class "Default")
      (node (ref "IC5") (pin "52") (pinfunction "PB13_52") (pintype "passive"))
    )
    (net (code "77") (name "unconnected-(IC5-PB14-Pad53)") (class "Default")
      (node (ref "IC5") (pin "53") (pinfunction "PB14_53") (pintype "passive"))
    )
    (net (code "78") (name "unconnected-(IC5-PB15-Pad54)") (class "Default")
      (node (ref "IC5") (pin "54") (pinfunction "PB15_54") (pintype "passive"))
    )
    (net (code "79") (name "unconnected-(IC5-PC0-Pad15)") (class "Default")
      (node (ref "IC5") (pin "15") (pinfunction "PC0_15") (pintype "passive"))
    )
    (net (code "80") (name "unconnected-(IC5-PC1-Pad16)") (class "Default")
      (node (ref "IC5") (pin "16") (pinfunction "PC1_16") (pintype "passive"))
    )
    (net (code "81") (name "unconnected-(IC5-PC2-Pad17)") (class "Default")
      (node (ref "IC5") (pin "17") (pinfunction "PC2_17") (pintype "passive"))
    )
    (net (code "82") (name "unconnected-(IC5-PC3-Pad18)") (class "Default")
      (node (ref "IC5") (pin "18") (pinfunction "PC3_18") (pintype "passive"))
    )
    (net (code "83") (name "unconnected-(IC5-PC4-Pad33)") (class "Default")
      (node (ref "IC5") (pin "33") (pinfunction "PC4_33") (pintype "passive"))
    )
    (net (code "84") (name "unconnected-(IC5-PC5-Pad34)") (class "Default")
      (node (ref "IC5") (pin "34") (pinfunction "PC5_34") (pintype "passive"))
    )
    (net (code "85") (name "unconnected-(IC5-PC13-Pad7)") (class "Default")
      (node (ref "IC5") (pin "7") (pinfunction "PC13_7") (pintype "passive"))
    )
    (net (code "86") (name "unconnected-(IC5-PC14-Pad8)") (class "Default")
      (node (ref "IC5") (pin "8") (pinfunction "PC14_8") (pintype "passive"))
    )
    (net (code "87") (name "unconnected-(IC5-PC15-Pad9)") (class "Default")
      (node (ref "IC5") (pin "9") (pinfunction "PC15_9") (pintype "passive"))
    )
    (net (code "88") (name "unconnected-(IC5-PD0-Pad81)") (class "Default")
      (node (ref "IC5") (pin "81") (pinfunction "PD0_81") (pintype "passive"))
    )
    (net (code "89") (name "unconnected-(IC5-PD2-Pad83)") (class "Default")
      (node (ref "IC5") (pin "83") (pinfunction "PD2_83") (pintype "passive"))
    )
    (net (code "90") (name "unconnected-(IC5-PD8-Pad55)") (class "Default")
      (node (ref "IC5") (pin "55") (pinfunction "PD8_55") (pintype "passive"))
    )
    (net (code "91") (name "unconnected-(IC5-PD9-Pad56)") (class "Default")
      (node (ref "IC5") (pin "56") (pinfunction "PD9_56") (pintype "passive"))
    )
    (net (code "92") (name "unconnected-(IC5-PD10-Pad57)") (class "Default")
      (node (ref "IC5") (pin "57") (pinfunction "PD10_57") (pintype "passive"))
    )
    (net (code "93") (name "unconnected-(IC5-PD11-Pad58)") (class "Default")
      (node (ref "IC5") (pin "58") (pinfunction "PD11_58") (pintype "passive"))
    )
    (net (code "94") (name "unconnected-(IC5-PD12-Pad59)") (class "Default")
      (node (ref "IC5") (pin "59") (pinfunction "PD12_59") (pintype "passive"))
    )
    (net (code "95") (name "unconnected-(IC5-PD13-Pad60)") (class "Default")
      (node (ref "IC5") (pin "60") (pinfunction "PD13_60") (pintype "passive"))
    )
    (net (code "96") (name "unconnected-(IC5-PD14-Pad61)") (class "Default")
      (node (ref "IC5") (pin "61") (pinfunction "PD14_61") (pintype "passive"))
    )
    (net (code "97") (name "unconnected-(IC5-PD15-Pad62)") (class "Default")
      (node (ref "IC5") (pin "62") (pinfunction "PD15_62") (pintype "passive"))
    )
    (net (code "98") (name "unconnected-(IC5-PE7-Pad38)") (class "Default")
      (node (ref "IC5") (pin "38") (pinfunction "PE7_38") (pintype "passive"))
    )
    (net (code "99") (name "unconnected-(IC5-PE8-Pad39)") (class "Default")
      (node (ref "IC5") (pin "39") (pinfunction "PE8_39") (pintype "passive"))
    )
    (net (code "100") (name "unconnected-(IC5-PE9-Pad40)") (class "Default")
      (node (ref "IC5") (pin "40") (pinfunction "PE9_40") (pintype "passive"))
    )
    (net (code "101") (name "unconnected-(IC5-PE10-Pad41)") (class "Default")
      (node (ref "IC5") (pin "41") (pinfunction "PE10_41") (pintype "passive"))
    )
    (net (code "102") (name "unconnected-(IC5-PE11-Pad42)") (class "Default")
      (node (ref "IC5") (pin "42") (pinfunction "PE11_42") (pintype "passive"))
    )
    (net (code "103") (name "unconnected-(IC5-PE12-Pad43)") (class "Default")
      (node (ref "IC5") (pin "43") (pinfunction "PE12_43") (pintype "passive"))
    )
    (net (code "104") (name "unconnected-(IC5-PE13-Pad44)") (class "Default")
      (node (ref "IC5") (pin "44") (pinfunction "PE13_44") (pintype "passive"))
    )
    (net (code "105") (name "unconnected-(IC5-PE14-Pad45)") (class "Default")
      (node (ref "IC5") (pin "45") (pinfunction "PE14_45") (pintype "passive"))
    )
    (net (code "106") (name "unconnected-(IC5-PE15-Pad46)") (class "Default")
      (node (ref "IC5") (pin "46") (pinfunction "PE15_46") (pintype "passive"))
    )
    (net (code "107") (name "unconnected-(J？-Pad8)") (class "Default")
      (node (ref "J？") (pin "8") (pinfunction "8_8") (pintype "passive"))
    )
  )
)
